# pmon_20v.net
KiCad netlist of a schematic drawn in EAGLE
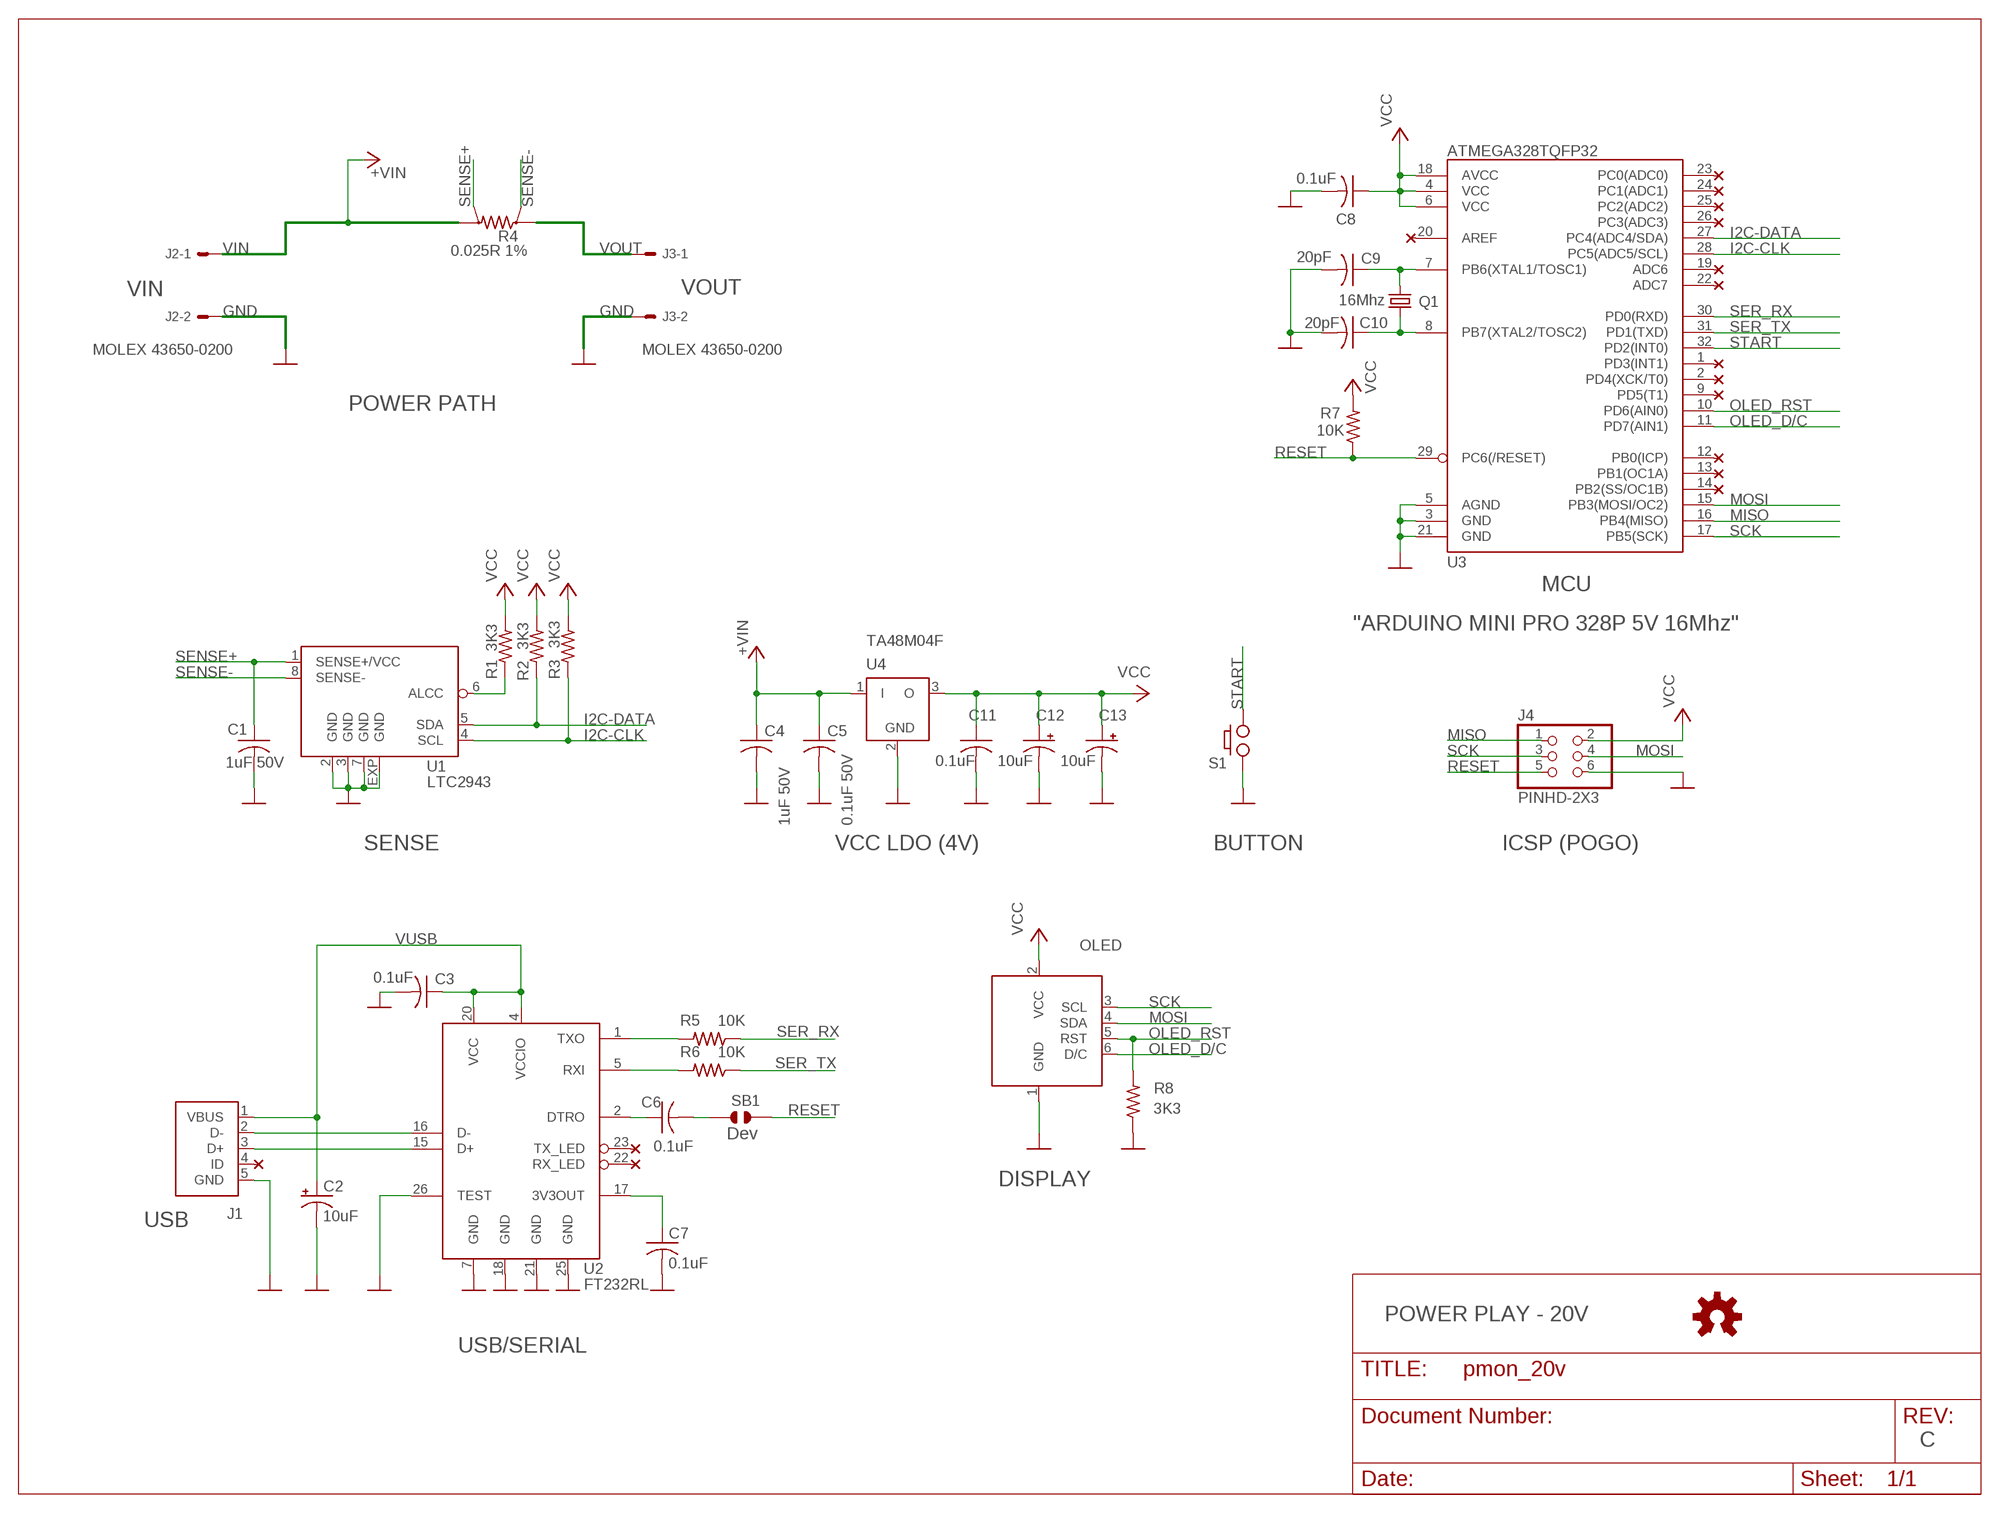
[diagram p0: schematic, sheet 1]

(export (version "E")
  (design (tool "Eeschema 10.0.6"))
  (components
    (comp (ref "C1")
      (value "1uF 50V")
      (footprint "eagle-import:C0603")
      (libsource (lib "eagle-import") (part "CAP-C0603"))
    )
    (comp (ref "C2")
      (value "10uF")
      (footprint "eagle-import:A_3216-18R")
      (libsource (lib "eagle-import") (part "CPOL-USA/3216-18R"))
    )
    (comp (ref "C3")
      (value "0.1uF")
      (footprint "eagle-import:C0603")
      (libsource (lib "eagle-import") (part "CAP-C0603"))
    )
    (comp (ref "C4")
      (value "1uF 50V")
      (footprint "eagle-import:C0603")
      (libsource (lib "eagle-import") (part "CAP-C0603"))
    )
    (comp (ref "C5")
      (value "0.1uF 50V")
      (footprint "eagle-import:C0603")
      (libsource (lib "eagle-import") (part "CAP-C0603"))
    )
    (comp (ref "C6")
      (value "0.1uF")
      (footprint "eagle-import:C0603")
      (libsource (lib "eagle-import") (part "CAP-C0603"))
    )
    (comp (ref "C7")
      (value "0.1uF")
      (footprint "eagle-import:C0603")
      (libsource (lib "eagle-import") (part "CAP-C0603"))
    )
    (comp (ref "C8")
      (value "0.1uF")
      (footprint "eagle-import:C0603")
      (libsource (lib "eagle-import") (part "CAP-C0603"))
    )
    (comp (ref "C9")
      (value "20pF")
      (footprint "eagle-import:C0603")
      (libsource (lib "eagle-import") (part "CAP-C0603"))
    )
    (comp (ref "C10")
      (value "20pF")
      (footprint "eagle-import:C0603")
      (libsource (lib "eagle-import") (part "CAP-C0603"))
    )
    (comp (ref "C11")
      (value "0.1uF")
      (footprint "eagle-import:C0603")
      (libsource (lib "eagle-import") (part "CAP-C0603"))
    )
    (comp (ref "C12")
      (value "10uF")
      (footprint "eagle-import:A_3216-18R")
      (libsource (lib "eagle-import") (part "CPOL-USA/3216-18R"))
    )
    (comp (ref "C13")
      (value "10uF")
      (footprint "eagle-import:A_3216-18R")
      (libsource (lib "eagle-import") (part "CPOL-USA/3216-18R"))
    )
    (comp (ref "J1")
      (value "USB")
      (footprint "eagle-import:USB-MICRO-ZX62RD-AB-5P8")
      (libsource (lib "eagle-import") (part "USB"))
    )
    (comp (ref "J2")
      (value "MOLEX 43650-0200")
      (footprint "eagle-import:POWER_CON")
      (libsource (lib "eagle-import") (part "POWER_CON27-2021"))
    )
    (comp (ref "J3")
      (value "MOLEX 43650-0200")
      (footprint "eagle-import:POWER_CON")
      (libsource (lib "eagle-import") (part "POWER_CON27-2021"))
    )
    (comp (ref "J4")
      (value "PINHD-2X3")
      (footprint "eagle-import:2X03")
      (libsource (lib "eagle-import") (part "PINHD-2X3"))
    )
    (comp (ref "OLED")
      (value "OLED")
      (footprint "eagle-import:OLED")
      (libsource (lib "eagle-import") (part "OLED"))
    )
    (comp (ref "Q1")
      (value "16Mhz")
      (footprint "eagle-import:CRYSTAL-CTS406")
      (libsource (lib "eagle-import") (part "CRYSTALCTS406"))
    )
    (comp (ref "R1")
      (value "3K3")
      (footprint "eagle-import:R0603")
      (libsource (lib "eagle-import") (part "RES-R0603"))
    )
    (comp (ref "R2")
      (value "3K3")
      (footprint "eagle-import:R0603")
      (libsource (lib "eagle-import") (part "RES-R0603"))
    )
    (comp (ref "R3")
      (value "3K3")
      (footprint "eagle-import:R0603")
      (libsource (lib "eagle-import") (part "RES-R0603"))
    )
    (comp (ref "R4")
      (value "0.025R 1%")
      (footprint "eagle-import:KELVIN-6432")
      (libsource (lib "eagle-import") (part "RES-SHUNT-6432"))
    )
    (comp (ref "R5")
      (value "10K")
      (footprint "eagle-import:R0603")
      (libsource (lib "eagle-import") (part "RES-R0603"))
    )
    (comp (ref "R6")
      (value "10K")
      (footprint "eagle-import:R0603")
      (libsource (lib "eagle-import") (part "RES-R0603"))
    )
    (comp (ref "R7")
      (value "10K")
      (footprint "eagle-import:R0603")
      (libsource (lib "eagle-import") (part "RES-R0603"))
    )
    (comp (ref "R8")
      (value "3K3")
      (footprint "eagle-import:R0603")
      (libsource (lib "eagle-import") (part "RES-R0603"))
    )
    (comp (ref "S1")
      (value "PUSH_BUTTON")
      (footprint "eagle-import:TLE1105")
      (libsource (lib "eagle-import") (part "PUSH_BUTTON"))
    )
    (comp (ref "SB1")
      (value "JUMPER_SOLDER_1X2")
      (footprint "eagle-import:JUMPER_SOLDER_1X2")
      (libsource (lib "eagle-import") (part "JUMPER_SOLDER_1X2"))
    )
    (comp (ref "U$28")
      (value "OSH")
      (footprint "eagle-import:OSH")
      (libsource (lib "eagle-import") (part "OSH"))
    )
    (comp (ref "U1")
      (value "LTC2943")
      (footprint "eagle-import:DFN8-3X3")
      (libsource (lib "eagle-import") (part "LTC2943"))
    )
    (comp (ref "U2")
      (value "FT232RL")
      (footprint "eagle-import:SSOP28DB")
      (libsource (lib "eagle-import") (part "FT232RL"))
    )
    (comp (ref "U3")
      (value "ATMEGA328TQFP32")
      (footprint "eagle-import:TQFP32-08")
      (libsource (lib "eagle-import") (part "ATMEGA328TQFP32"))
    )
    (comp (ref "U4")
      (value "TA48M04F")
      (footprint "eagle-import:DPACK")
      (libsource (lib "eagle-import") (part "LP2950"))
    )
  )
  (nets
    (net (code "1") (name "+VIN") (class "Default")
      (node (ref "C4") (pin "1") (pinfunction "1_1") (pintype "passive"))
      (node (ref "C5") (pin "1") (pinfunction "1_1") (pintype "passive"))
      (node (ref "J2") (pin "1") (pinfunction "S_1") (pintype "passive"))
      (node (ref "R4") (pin "I2") (pinfunction "I2_I2") (pintype "passive"))
      (node (ref "U4") (pin "1") (pinfunction "I_1") (pintype "input"))
    )
    (net (code "2") (name "/AREF") (class "Default")
      (node (ref "U3") (pin "20") (pinfunction "AREF_20") (pintype "power_in"))
    )
    (net (code "3") (name "/I2C-CLK") (class "Default")
      (node (ref "R3") (pin "1") (pinfunction "1_1") (pintype "passive"))
      (node (ref "U1") (pin "4") (pinfunction "SCL_4") (pintype "input"))
      (node (ref "U3") (pin "28") (pinfunction "PC5(ADC5/SCL)_28") (pintype "bidirectional"))
    )
    (net (code "4") (name "/I2C-DATA") (class "Default")
      (node (ref "R2") (pin "1") (pinfunction "1_1") (pintype "passive"))
      (node (ref "U1") (pin "5") (pinfunction "SDA_5") (pintype "bidirectional"))
      (node (ref "U3") (pin "27") (pinfunction "PC4(ADC4/SDA)_27") (pintype "bidirectional"))
    )
    (net (code "5") (name "/MISO") (class "Default")
      (node (ref "J4") (pin "1") (pinfunction "1_1") (pintype "passive"))
      (node (ref "U3") (pin "16") (pinfunction "PB4(MISO)_16") (pintype "bidirectional"))
    )
    (net (code "6") (name "/MOSI") (class "Default")
      (node (ref "J4") (pin "4") (pinfunction "4_4") (pintype "passive"))
      (node (ref "OLED") (pin "4") (pinfunction "SDA_4") (pintype "input"))
      (node (ref "U3") (pin "15") (pinfunction "PB3(MOSI/OC2)_15") (pintype "bidirectional"))
    )
    (net (code "7") (name "/OLED_D{slash}C") (class "Default")
      (node (ref "OLED") (pin "6") (pinfunction "D/C_6") (pintype "input"))
      (node (ref "U3") (pin "11") (pinfunction "PD7(AIN1)_11") (pintype "bidirectional"))
    )
    (net (code "8") (name "/OLED_RST") (class "Default")
      (node (ref "OLED") (pin "5") (pinfunction "RST_5") (pintype "input"))
      (node (ref "R8") (pin "2") (pinfunction "2_2") (pintype "passive"))
      (node (ref "U3") (pin "10") (pinfunction "PD6(AIN0)_10") (pintype "bidirectional"))
    )
    (net (code "9") (name "/RESET") (class "Default")
      (node (ref "J4") (pin "5") (pinfunction "5_5") (pintype "passive"))
      (node (ref "R7") (pin "1") (pinfunction "1_1") (pintype "passive"))
      (node (ref "SB1") (pin "2") (pinfunction "2_2") (pintype "passive"))
      (node (ref "U3") (pin "29") (pinfunction "PC6(/RESET)_29") (pintype "bidirectional"))
    )
    (net (code "10") (name "/SCK") (class "Default")
      (node (ref "J4") (pin "3") (pinfunction "3_3") (pintype "passive"))
      (node (ref "OLED") (pin "3") (pinfunction "SCL_3") (pintype "input"))
      (node (ref "U3") (pin "17") (pinfunction "PB5(SCK)_17") (pintype "bidirectional"))
    )
    (net (code "11") (name "/SENSE+") (class "Default")
      (node (ref "C1") (pin "1") (pinfunction "1_1") (pintype "passive"))
      (node (ref "R4") (pin "V2") (pinfunction "V2_V2") (pintype "passive"))
      (node (ref "U1") (pin "1") (pinfunction "SENSE+/VCC_1") (pintype "passive"))
    )
    (net (code "12") (name "/SENSE-") (class "Default")
      (node (ref "R4") (pin "V1") (pinfunction "V1_V1") (pintype "passive"))
      (node (ref "U1") (pin "8") (pinfunction "SENSE-_8") (pintype "passive"))
    )
    (net (code "13") (name "/SER_RX") (class "Default")
      (node (ref "R5") (pin "1") (pinfunction "1_1") (pintype "passive"))
      (node (ref "U3") (pin "30") (pinfunction "PD0(RXD)_30") (pintype "bidirectional"))
    )
    (net (code "14") (name "/SER_TX") (class "Default")
      (node (ref "R6") (pin "1") (pinfunction "1_1") (pintype "passive"))
      (node (ref "U3") (pin "31") (pinfunction "PD1(TXD)_31") (pintype "bidirectional"))
    )
    (net (code "15") (name "/START") (class "Default")
      (node (ref "S1") (pin "B") (pinfunction "2_B") (pintype "passive"))
      (node (ref "U3") (pin "32") (pinfunction "PD2(INT0)_32") (pintype "bidirectional"))
    )
    (net (code "16") (name "/VOUT") (class "Default")
      (node (ref "J3") (pin "1") (pinfunction "S_1") (pintype "passive"))
      (node (ref "R4") (pin "I1") (pinfunction "I1_I1") (pintype "passive"))
    )
    (net (code "17") (name "/VUSB") (class "Default")
      (node (ref "C2") (pin "+") (pinfunction "+_+") (pintype "passive"))
      (node (ref "C3") (pin "1") (pinfunction "1_1") (pintype "passive"))
      (node (ref "J1") (pin "1") (pinfunction "VBUS_1") (pintype "bidirectional"))
      (node (ref "U2") (pin "20") (pinfunction "VCC_20") (pintype "power_in"))
      (node (ref "U2") (pin "4") (pinfunction "VCCIO_4") (pintype "power_in"))
    )
    (net (code "18") (name "GND") (class "Default")
      (node (ref "C1") (pin "2") (pinfunction "2_2") (pintype "passive"))
      (node (ref "C10") (pin "2") (pinfunction "2_2") (pintype "passive"))
      (node (ref "C11") (pin "2") (pinfunction "2_2") (pintype "passive"))
      (node (ref "C12") (pin "-") (pinfunction "-_-") (pintype "passive"))
      (node (ref "C13") (pin "-") (pinfunction "-_-") (pintype "passive"))
      (node (ref "C2") (pin "-") (pinfunction "-_-") (pintype "passive"))
      (node (ref "C3") (pin "2") (pinfunction "2_2") (pintype "passive"))
      (node (ref "C4") (pin "2") (pinfunction "2_2") (pintype "passive"))
      (node (ref "C5") (pin "2") (pinfunction "2_2") (pintype "passive"))
      (node (ref "C7") (pin "2") (pinfunction "2_2") (pintype "passive"))
      (node (ref "C8") (pin "2") (pinfunction "2_2") (pintype "passive"))
      (node (ref "C9") (pin "2") (pinfunction "2_2") (pintype "passive"))
      (node (ref "J1") (pin "5") (pinfunction "GND_5") (pintype "bidirectional"))
      (node (ref "J2") (pin "2") (pinfunction "S_2") (pintype "passive"))
      (node (ref "J3") (pin "2") (pinfunction "S_2") (pintype "passive"))
      (node (ref "J4") (pin "6") (pinfunction "6_6") (pintype "passive"))
      (node (ref "OLED") (pin "1") (pinfunction "GND_1") (pintype "power_in"))
      (node (ref "R8") (pin "1") (pinfunction "1_1") (pintype "passive"))
      (node (ref "S1") (pin "A") (pinfunction "1_A") (pintype "passive"))
      (node (ref "U1") (pin "2") (pinfunction "GND_2") (pintype "power_in"))
      (node (ref "U1") (pin "3") (pinfunction "GND_3") (pintype "power_in"))
      (node (ref "U1") (pin "7") (pinfunction "GND_7") (pintype "power_in"))
      (node (ref "U1") (pin "EXP") (pinfunction "GND_EXP") (pintype "power_in"))
      (node (ref "U2") (pin "18") (pinfunction "GND_18") (pintype "power_in"))
      (node (ref "U2") (pin "21") (pinfunction "GND_21") (pintype "power_in"))
      (node (ref "U2") (pin "25") (pinfunction "GND_25") (pintype "power_in"))
      (node (ref "U2") (pin "26") (pinfunction "TEST_26") (pintype "input"))
      (node (ref "U2") (pin "7") (pinfunction "GND_7") (pintype "power_in"))
      (node (ref "U3") (pin "21") (pinfunction "GND_21") (pintype "power_in"))
      (node (ref "U3") (pin "3") (pinfunction "GND_3") (pintype "power_in"))
      (node (ref "U3") (pin "5") (pinfunction "AGND_5") (pintype "power_in"))
      (node (ref "U4") (pin "2") (pinfunction "GND_2") (pintype "power_in"))
    )
    (net (code "19") (name "Net-(C6-Pad2)") (class "Default")
      (node (ref "C6") (pin "2") (pinfunction "2_2") (pintype "passive"))
      (node (ref "SB1") (pin "1") (pinfunction "1_1") (pintype "passive"))
    )
    (net (code "20") (name "Net-(J1-D+)") (class "Default")
      (node (ref "J1") (pin "3") (pinfunction "D+_3") (pintype "bidirectional"))
      (node (ref "U2") (pin "15") (pinfunction "D+_15") (pintype "passive"))
    )
    (net (code "21") (name "Net-(J1-D-)") (class "Default")
      (node (ref "J1") (pin "2") (pinfunction "D-_2") (pintype "bidirectional"))
      (node (ref "U2") (pin "16") (pinfunction "D-_16") (pintype "passive"))
    )
    (net (code "22") (name "Net-(Q1-2)") (class "Default")
      (node (ref "C10") (pin "1") (pinfunction "1_1") (pintype "passive"))
      (node (ref "Q1") (pin "3") (pinfunction "2_3") (pintype "passive"))
      (node (ref "U3") (pin "8") (pinfunction "PB7(XTAL2/TOSC2)_8") (pintype "bidirectional"))
    )
    (net (code "23") (name "Net-(U1-ALCC)") (class "Default")
      (node (ref "R1") (pin "1") (pinfunction "1_1") (pintype "passive"))
      (node (ref "U1") (pin "6") (pinfunction "ALCC_6") (pintype "open_collector"))
    )
    (net (code "24") (name "Net-(U2-3V3OUT)") (class "Default")
      (node (ref "C7") (pin "1") (pinfunction "1_1") (pintype "passive"))
      (node (ref "U2") (pin "17") (pinfunction "3V3OUT_17") (pintype "power_in"))
    )
    (net (code "25") (name "Net-(U2-DTRO)") (class "Default")
      (node (ref "C6") (pin "1") (pinfunction "1_1") (pintype "passive"))
      (node (ref "U2") (pin "2") (pinfunction "DTRO_2") (pintype "output"))
    )
    (net (code "26") (name "Net-(U2-RXI)") (class "Default")
      (node (ref "R6") (pin "2") (pinfunction "2_2") (pintype "passive"))
      (node (ref "U2") (pin "5") (pinfunction "RXI_5") (pintype "input"))
    )
    (net (code "27") (name "Net-(U2-TXO)") (class "Default")
      (node (ref "R5") (pin "2") (pinfunction "2_2") (pintype "passive"))
      (node (ref "U2") (pin "1") (pinfunction "TXO_1") (pintype "output"))
    )
    (net (code "28") (name "Net-(U3-PB6(XTAL1{slash}TOSC1))") (class "Default")
      (node (ref "C9") (pin "1") (pinfunction "1_1") (pintype "passive"))
      (node (ref "Q1") (pin "1") (pinfunction "1_1") (pintype "passive"))
      (node (ref "U3") (pin "7") (pinfunction "PB6(XTAL1/TOSC1)_7") (pintype "bidirectional"))
    )
    (net (code "29") (name "VCC") (class "Default")
      (node (ref "C11") (pin "1") (pinfunction "1_1") (pintype "passive"))
      (node (ref "C12") (pin "+") (pinfunction "+_+") (pintype "passive"))
      (node (ref "C13") (pin "+") (pinfunction "+_+") (pintype "passive"))
      (node (ref "C8") (pin "1") (pinfunction "1_1") (pintype "passive"))
      (node (ref "J4") (pin "2") (pinfunction "2_2") (pintype "passive"))
      (node (ref "OLED") (pin "2") (pinfunction "VCC_2") (pintype "power_in"))
      (node (ref "R1") (pin "2") (pinfunction "2_2") (pintype "passive"))
      (node (ref "R2") (pin "2") (pinfunction "2_2") (pintype "passive"))
      (node (ref "R3") (pin "2") (pinfunction "2_2") (pintype "passive"))
      (node (ref "R7") (pin "2") (pinfunction "2_2") (pintype "passive"))
      (node (ref "U3") (pin "18") (pinfunction "AVCC_18") (pintype "power_in"))
      (node (ref "U3") (pin "4") (pinfunction "VCC_4") (pintype "power_in"))
      (node (ref "U3") (pin "6") (pinfunction "VCC_6") (pintype "power_in"))
      (node (ref "U4") (pin "3") (pinfunction "O_3") (pintype "input"))
    )
    (net (code "30") (name "unconnected-(J1-ID-Pad4)") (class "Default")
      (node (ref "J1") (pin "4") (pinfunction "ID_4") (pintype "bidirectional"))
    )
    (net (code "31") (name "unconnected-(U2-RX_LED-Pad22)") (class "Default")
      (node (ref "U2") (pin "22") (pinfunction "RX_LED_22") (pintype "output"))
    )
    (net (code "32") (name "unconnected-(U2-TX_LED-Pad23)") (class "Default")
      (node (ref "U2") (pin "23") (pinfunction "TX_LED_23") (pintype "output"))
    )
    (net (code "33") (name "unconnected-(U3-ADC6-Pad19)") (class "Default")
      (node (ref "U3") (pin "19") (pinfunction "ADC6_19") (pintype "bidirectional"))
    )
    (net (code "34") (name "unconnected-(U3-ADC7-Pad22)") (class "Default")
      (node (ref "U3") (pin "22") (pinfunction "ADC7_22") (pintype "bidirectional"))
    )
    (net (code "35") (name "unconnected-(U3-PB0(ICP)-Pad12)") (class "Default")
      (node (ref "U3") (pin "12") (pinfunction "PB0(ICP)_12") (pintype "bidirectional"))
    )
    (net (code "36") (name "unconnected-(U3-PB1(OC1A)-Pad13)") (class "Default")
      (node (ref "U3") (pin "13") (pinfunction "PB1(OC1A)_13") (pintype "bidirectional"))
    )
    (net (code "37") (name "unconnected-(U3-PB2(SS{slash}OC1B)-Pad14)") (class "Default")
      (node (ref "U3") (pin "14") (pinfunction "PB2(SS/OC1B)_14") (pintype "bidirectional"))
    )
    (net (code "38") (name "unconnected-(U3-PC0(ADC0)-Pad23)") (class "Default")
      (node (ref "U3") (pin "23") (pinfunction "PC0(ADC0)_23") (pintype "bidirectional"))
    )
    (net (code "39") (name "unconnected-(U3-PC1(ADC1)-Pad24)") (class "Default")
      (node (ref "U3") (pin "24") (pinfunction "PC1(ADC1)_24") (pintype "bidirectional"))
    )
    (net (code "40") (name "unconnected-(U3-PC2(ADC2)-Pad25)") (class "Default")
      (node (ref "U3") (pin "25") (pinfunction "PC2(ADC2)_25") (pintype "bidirectional"))
    )
    (net (code "41") (name "unconnected-(U3-PC3(ADC3)-Pad26)") (class "Default")
      (node (ref "U3") (pin "26") (pinfunction "PC3(ADC3)_26") (pintype "bidirectional"))
    )
    (net (code "42") (name "unconnected-(U3-PD3(INT1)-Pad1)") (class "Default")
      (node (ref "U3") (pin "1") (pinfunction "PD3(INT1)_1") (pintype "bidirectional"))
    )
    (net (code "43") (name "unconnected-(U3-PD4(XCK{slash}T0)-Pad2)") (class "Default")
      (node (ref "U3") (pin "2") (pinfunction "PD4(XCK/T0)_2") (pintype "bidirectional"))
    )
    (net (code "44") (name "unconnected-(U3-PD5(T1)-Pad9)") (class "Default")
      (node (ref "U3") (pin "9") (pinfunction "PD5(T1)_9") (pintype "bidirectional"))
    )
  )
)
